# shematic_easyeda_file.net
KiCad netlist of a schematic drawn in EasyEDA
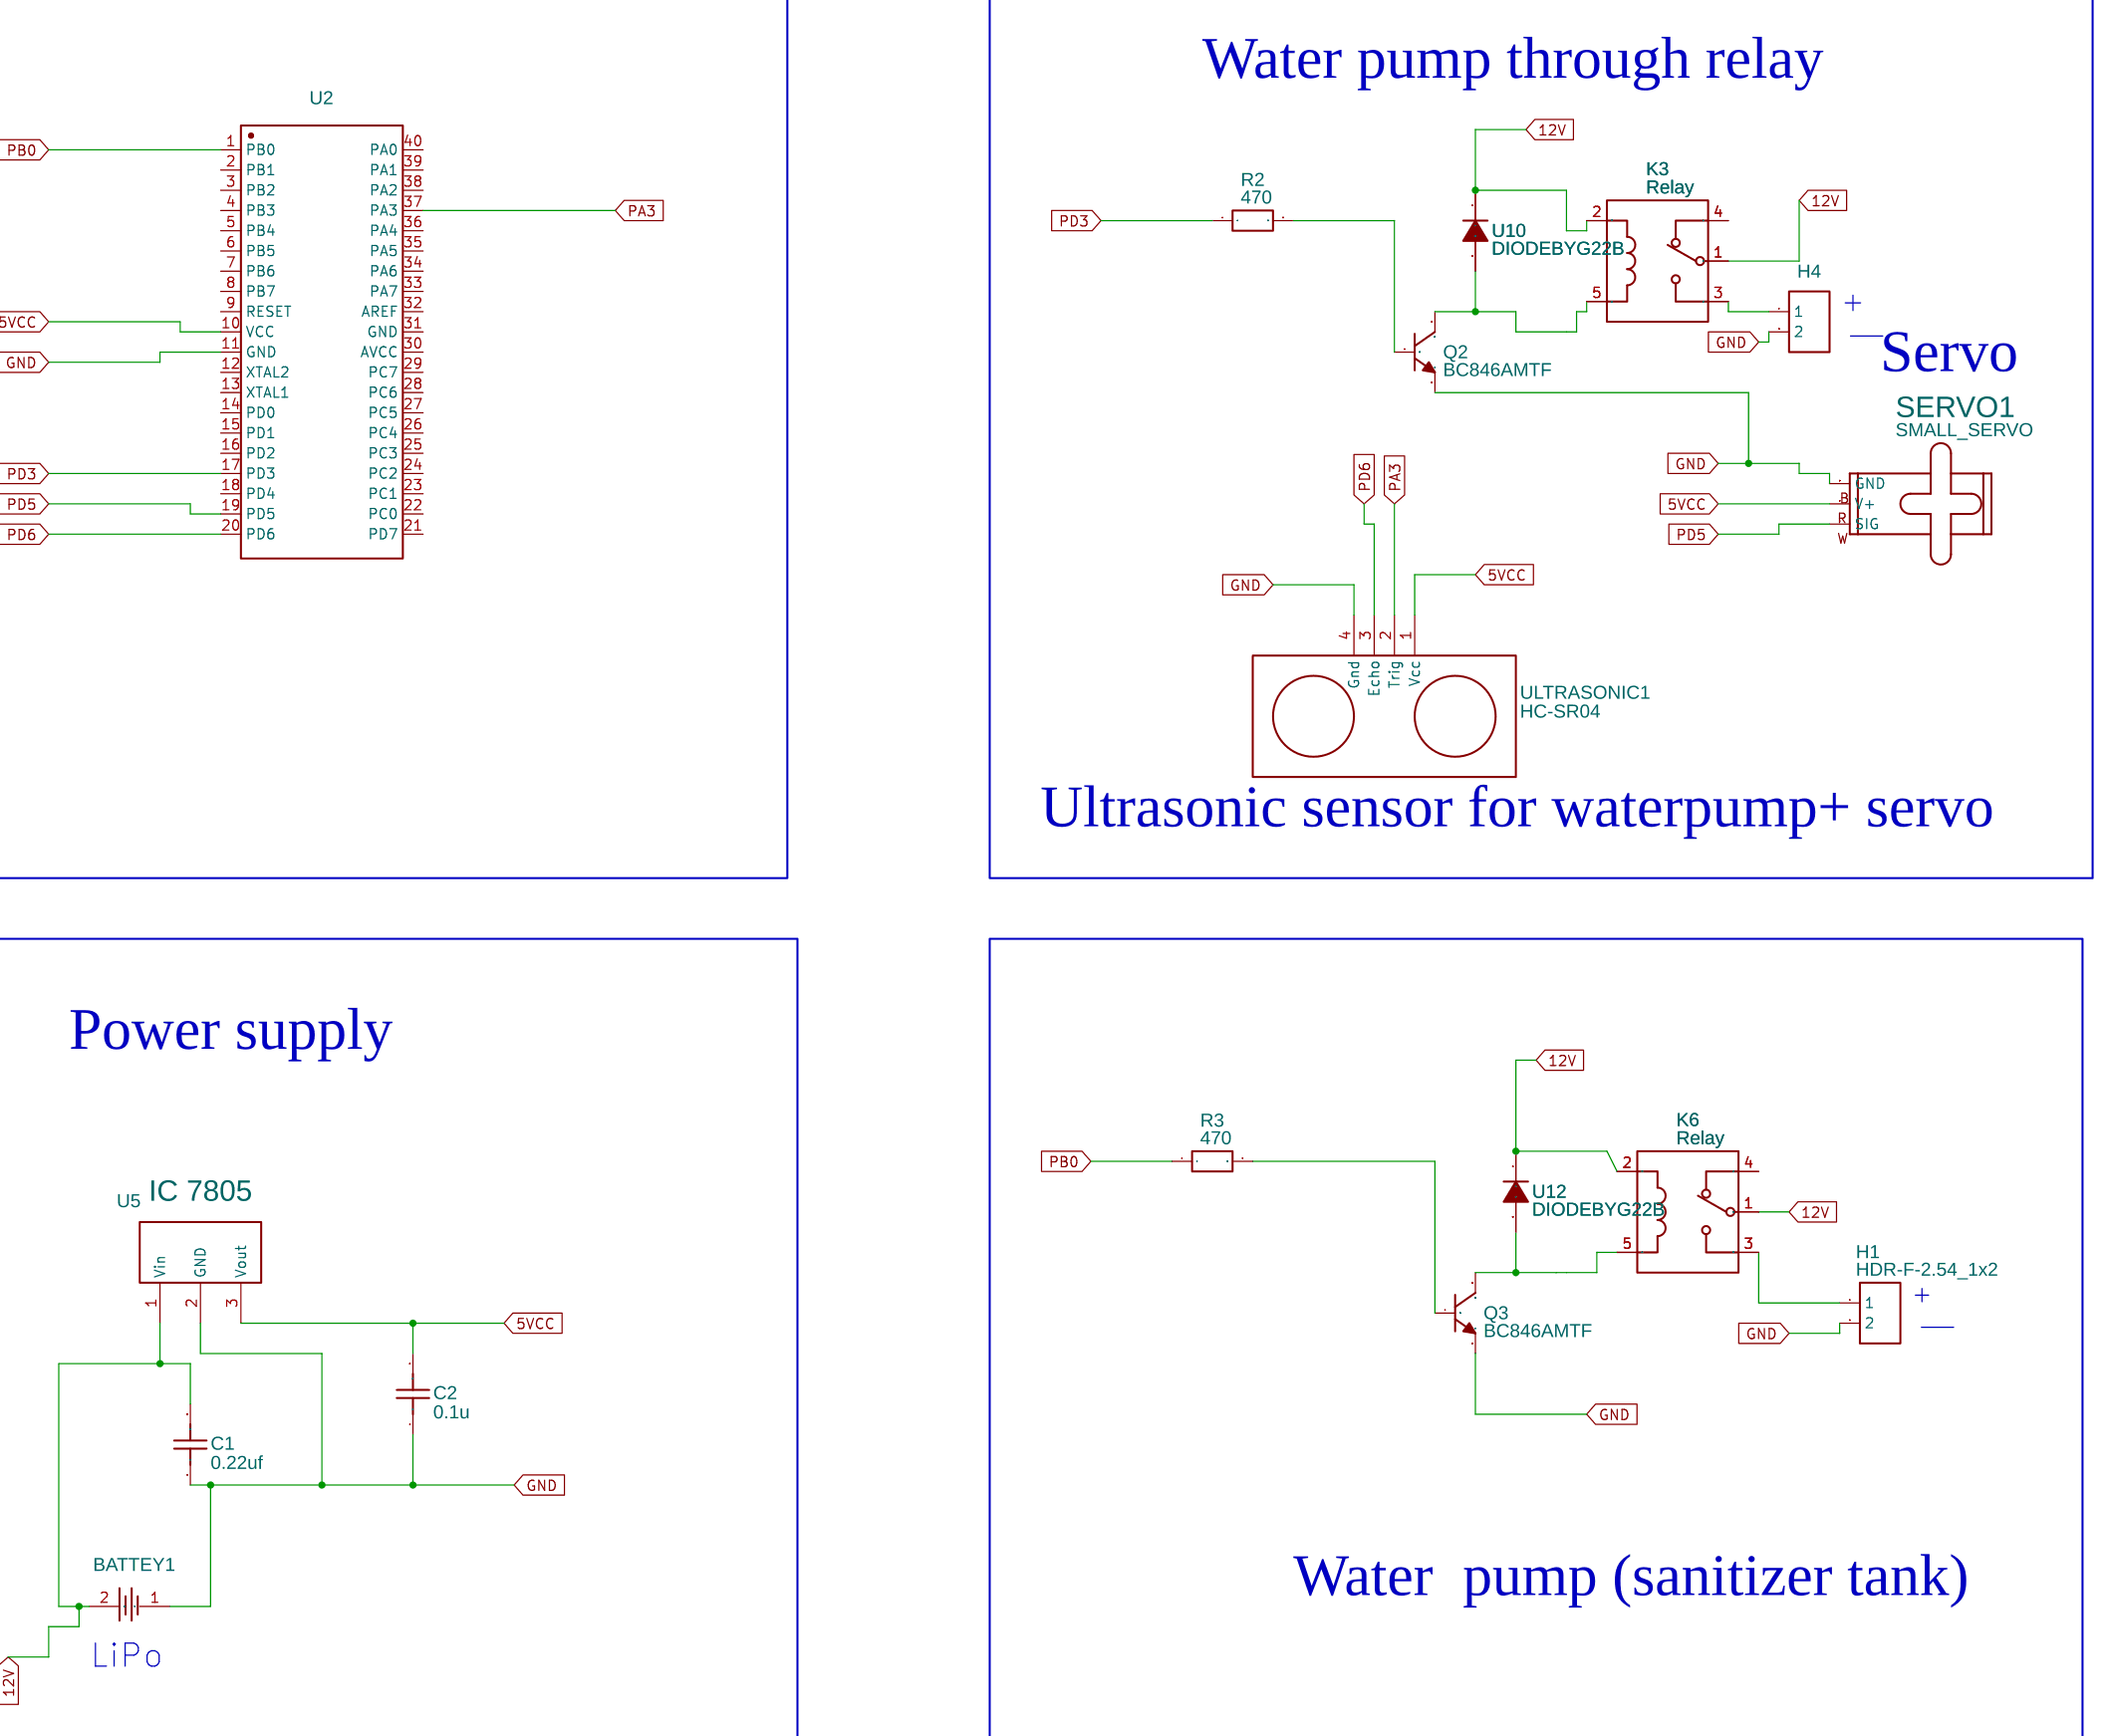
[diagram p0: schematic sheet]

(export (version "E")
  (design (tool "Eeschema 10.0.6"))
  (components
    (comp (ref "BATTEY1")
      (value "BH-18650-B1BA002")
      (fields (field (name "BOM_Supplier Part") "C2988620"))
      (libsource (lib "") (part "BH-18650-B1BA002"))
    )
    (comp (ref "C1") (value "0.22uf") (libsource (lib "") (part "C_0603_US")))
    (comp (ref "C2") (value "0.1u") (libsource (lib "") (part "C_0603_US")))
    (comp (ref "H1")
      (value "HDR-F-2.54_1x2")
      (fields (field (name "BOM_Supplier Part") "C49661"))
      (libsource (lib "") (part "HDR-F-2.54_1x2"))
    )
    (comp (ref "H4")
      (value "HDR-F-2.54_1x2")
      (fields (field (name "BOM_Supplier Part") "C49661"))
      (libsource (lib "") (part "HDR-F-2.54_1x2"))
    )
    (comp (ref "K3")
      (value "Relay")
      (fields
        (field (name "BOM_Manufacturer Part") "RelayHT3F-12VDC-SHG")
        (field (name "BOM_Supplier Part") "C22022")
      )
      (libsource (lib "") (part "Unknown_890_-685"))
    )
    (comp (ref "K6")
      (value "Relay")
      (fields
        (field (name "BOM_Manufacturer Part") "RelayHT3F-12VDC-SHG")
        (field (name "BOM_Supplier Part") "C22022")
      )
      (libsource (lib "") (part "Unknown_905_-215"))
    )
    (comp (ref "Q2")
      (value "BC846AMTF")
      (fields (field (name "BOM_Supplier Part") "C184441"))
      (libsource (lib "") (part "BC846AMTF"))
    )
    (comp (ref "Q3")
      (value "BC846AMTF")
      (fields (field (name "BOM_Supplier Part") "C184441"))
      (libsource (lib "") (part "BC846AMTF"))
    )
    (comp (ref "R2") (value "470") (libsource (lib "") (part "R_0603_EU")))
    (comp (ref "R3") (value "470") (libsource (lib "") (part "R_0603_EU")))
    (comp (ref "SERVO1") (value "SMALL_SERVO") (libsource (lib "") (part "SMALL_SERVO")))
    (comp (ref "U2")
      (value "ATMEGA32A-PU")
      (fields (field (name "BOM_Supplier Part") "C12703"))
      (libsource (lib "") (part "Unknown_225_-645"))
    )
    (comp (ref "U5")
      (value "IC 7805")
      (fields
        (field (name "BOM_Manufacturer Part") "K78X6-500R2")
        (field (name "BOM_Supplier Part") "C64019")
      )
      (libsource (lib "") (part "K78X6-500R2"))
    )
    (comp (ref "U10")
      (value "DIODEBYG22B")
      (fields
        (field (name "BOM_Manufacturer Part") "DiodeBYG22B")
        (field (name "BOM_Supplier Part") "C9900013935")
      )
      (libsource (lib "") (part "DIODEBYG22B"))
    )
    (comp (ref "U12")
      (value "DIODEBYG22B")
      (fields
        (field (name "BOM_Manufacturer Part") "DiodeBYG22B")
        (field (name "BOM_Supplier Part") "C9900013935")
      )
      (libsource (lib "") (part "DIODEBYG22B"))
    )
    (comp (ref "ULTRASONIC1") (value "HC-SR04") (libsource (lib "") (part "HC-SR04")))
  )
  (nets
    (net (code "1") (name "5VCC") (class "Default")
      (node (ref "C2") (pin "2") (pinfunction "2_2") (pintype "unspecified"))
      (node (ref "SERVO1") (pin "2") (pinfunction "V+_2") (pintype "unspecified"))
      (node (ref "U2") (pin "10") (pinfunction "VCC_10") (pintype "unspecified"))
      (node (ref "U5") (pin "3") (pinfunction "Vout_3") (pintype "unspecified"))
      (node (ref "ULTRASONIC1") (pin "1") (pinfunction "Vcc_1") (pintype "unspecified"))
    )
    (net (code "2") (name "12V") (class "Default")
      (node (ref "BATTEY1") (pin "2") (pinfunction "2_2") (pintype "input"))
      (node (ref "C1") (pin "2") (pinfunction "2_2") (pintype "unspecified"))
      (node (ref "K3") (pin "1") (pinfunction "1_1") (pintype "unspecified"))
      (node (ref "K3") (pin "2") (pinfunction "2_2") (pintype "unspecified"))
      (node (ref "K6") (pin "1") (pinfunction "1_1") (pintype "unspecified"))
      (node (ref "K6") (pin "2") (pinfunction "2_2") (pintype "unspecified"))
      (node (ref "U10") (pin "1") (pinfunction "K_1") (pintype "unspecified"))
      (node (ref "U12") (pin "1") (pinfunction "K_1") (pintype "unspecified"))
      (node (ref "U5") (pin "1") (pinfunction "Vin_1") (pintype "unspecified"))
    )
    (net (code "3") (name "GND") (class "Default")
      (node (ref "BATTEY1") (pin "1") (pinfunction "1_1") (pintype "input"))
      (node (ref "C1") (pin "1") (pinfunction "1_1") (pintype "unspecified"))
      (node (ref "C2") (pin "1") (pinfunction "1_1") (pintype "unspecified"))
      (node (ref "H1") (pin "2") (pinfunction "2_2") (pintype "input"))
      (node (ref "H4") (pin "2") (pinfunction "2_2") (pintype "input"))
      (node (ref "Q2") (pin "2") (pinfunction "E_2") (pintype "unspecified"))
      (node (ref "Q3") (pin "2") (pinfunction "E_2") (pintype "unspecified"))
      (node (ref "SERVO1") (pin "3") (pinfunction "GND_3") (pintype "unspecified"))
      (node (ref "U2") (pin "11") (pinfunction "GND_11") (pintype "unspecified"))
      (node (ref "U5") (pin "2") (pinfunction "GND_2") (pintype "unspecified"))
      (node (ref "ULTRASONIC1") (pin "4") (pinfunction "Gnd_4") (pintype "unspecified"))
    )
    (net (code "4") (name "Net-(H1-Pad1)") (class "Default")
      (node (ref "H1") (pin "1") (pinfunction "1_1") (pintype "input"))
      (node (ref "K6") (pin "3") (pinfunction "3_3") (pintype "unspecified"))
    )
    (net (code "5") (name "Net-(H4-Pad1)") (class "Default")
      (node (ref "H4") (pin "1") (pinfunction "1_1") (pintype "input"))
      (node (ref "K3") (pin "3") (pinfunction "3_3") (pintype "unspecified"))
    )
    (net (code "6") (name "Net-(Q2-B)") (class "Default")
      (node (ref "Q2") (pin "1") (pinfunction "B_1") (pintype "unspecified"))
      (node (ref "R2") (pin "2") (pinfunction "2_2") (pintype "unspecified"))
    )
    (net (code "7") (name "Net-(Q2-C)") (class "Default")
      (node (ref "K3") (pin "5") (pinfunction "5_5") (pintype "unspecified"))
      (node (ref "Q2") (pin "3") (pinfunction "C_3") (pintype "unspecified"))
      (node (ref "U10") (pin "2") (pinfunction "A_2") (pintype "unspecified"))
    )
    (net (code "8") (name "Net-(Q3-B)") (class "Default")
      (node (ref "Q3") (pin "1") (pinfunction "B_1") (pintype "unspecified"))
      (node (ref "R3") (pin "2") (pinfunction "2_2") (pintype "unspecified"))
    )
    (net (code "9") (name "Net-(Q3-C)") (class "Default")
      (node (ref "K6") (pin "5") (pinfunction "5_5") (pintype "unspecified"))
      (node (ref "Q3") (pin "3") (pinfunction "C_3") (pintype "unspecified"))
      (node (ref "U12") (pin "2") (pinfunction "A_2") (pintype "unspecified"))
    )
    (net (code "10") (name "PA3") (class "Default")
      (node (ref "U2") (pin "37") (pinfunction "PA3_37") (pintype "unspecified"))
      (node (ref "ULTRASONIC1") (pin "2") (pinfunction "Trig_2") (pintype "unspecified"))
    )
    (net (code "11") (name "PB0") (class "Default")
      (node (ref "R3") (pin "1") (pinfunction "1_1") (pintype "unspecified"))
      (node (ref "U2") (pin "1") (pinfunction "PB0_1") (pintype "unspecified"))
    )
    (net (code "12") (name "PD3") (class "Default")
      (node (ref "R2") (pin "1") (pinfunction "1_1") (pintype "unspecified"))
      (node (ref "U2") (pin "17") (pinfunction "PD3_17") (pintype "unspecified"))
    )
    (net (code "13") (name "PD5") (class "Default")
      (node (ref "SERVO1") (pin "1") (pinfunction "SIG_1") (pintype "unspecified"))
      (node (ref "U2") (pin "19") (pinfunction "PD5_19") (pintype "unspecified"))
    )
    (net (code "14") (name "PD6") (class "Default")
      (node (ref "U2") (pin "20") (pinfunction "PD6_20") (pintype "unspecified"))
      (node (ref "ULTRASONIC1") (pin "3") (pinfunction "Echo_3") (pintype "unspecified"))
    )
    (net (code "15") (name "unconnected-(K3-Pad4)") (class "Default")
      (node (ref "K3") (pin "4") (pinfunction "4_4") (pintype "unspecified"))
    )
    (net (code "16") (name "unconnected-(K6-Pad4)") (class "Default")
      (node (ref "K6") (pin "4") (pinfunction "4_4") (pintype "unspecified"))
    )
    (net (code "17") (name "unconnected-(U2-AREF-Pad32)") (class "Default")
      (node (ref "U2") (pin "32") (pinfunction "AREF_32") (pintype "unspecified"))
    )
    (net (code "18") (name "unconnected-(U2-AVCC-Pad30)") (class "Default")
      (node (ref "U2") (pin "30") (pinfunction "AVCC_30") (pintype "unspecified"))
    )
    (net (code "19") (name "unconnected-(U2-GND-Pad31)") (class "Default")
      (node (ref "U2") (pin "31") (pinfunction "GND_31") (pintype "unspecified"))
    )
    (net (code "20") (name "unconnected-(U2-PA0-Pad40)") (class "Default")
      (node (ref "U2") (pin "40") (pinfunction "PA0_40") (pintype "unspecified"))
    )
    (net (code "21") (name "unconnected-(U2-PA1-Pad39)") (class "Default")
      (node (ref "U2") (pin "39") (pinfunction "PA1_39") (pintype "unspecified"))
    )
    (net (code "22") (name "unconnected-(U2-PA2-Pad38)") (class "Default")
      (node (ref "U2") (pin "38") (pinfunction "PA2_38") (pintype "unspecified"))
    )
    (net (code "23") (name "unconnected-(U2-PA4-Pad36)") (class "Default")
      (node (ref "U2") (pin "36") (pinfunction "PA4_36") (pintype "unspecified"))
    )
    (net (code "24") (name "unconnected-(U2-PA5-Pad35)") (class "Default")
      (node (ref "U2") (pin "35") (pinfunction "PA5_35") (pintype "unspecified"))
    )
    (net (code "25") (name "unconnected-(U2-PA6-Pad34)") (class "Default")
      (node (ref "U2") (pin "34") (pinfunction "PA6_34") (pintype "unspecified"))
    )
    (net (code "26") (name "unconnected-(U2-PA7-Pad33)") (class "Default")
      (node (ref "U2") (pin "33") (pinfunction "PA7_33") (pintype "unspecified"))
    )
    (net (code "27") (name "unconnected-(U2-PB1-Pad2)") (class "Default")
      (node (ref "U2") (pin "2") (pinfunction "PB1_2") (pintype "unspecified"))
    )
    (net (code "28") (name "unconnected-(U2-PB2-Pad3)") (class "Default")
      (node (ref "U2") (pin "3") (pinfunction "PB2_3") (pintype "unspecified"))
    )
    (net (code "29") (name "unconnected-(U2-PB3-Pad4)") (class "Default")
      (node (ref "U2") (pin "4") (pinfunction "PB3_4") (pintype "unspecified"))
    )
    (net (code "30") (name "unconnected-(U2-PB4-Pad5)") (class "Default")
      (node (ref "U2") (pin "5") (pinfunction "PB4_5") (pintype "unspecified"))
    )
    (net (code "31") (name "unconnected-(U2-PB5-Pad6)") (class "Default")
      (node (ref "U2") (pin "6") (pinfunction "PB5_6") (pintype "unspecified"))
    )
    (net (code "32") (name "unconnected-(U2-PB6-Pad7)") (class "Default")
      (node (ref "U2") (pin "7") (pinfunction "PB6_7") (pintype "unspecified"))
    )
    (net (code "33") (name "unconnected-(U2-PB7-Pad8)") (class "Default")
      (node (ref "U2") (pin "8") (pinfunction "PB7_8") (pintype "unspecified"))
    )
    (net (code "34") (name "unconnected-(U2-PC0-Pad22)") (class "Default")
      (node (ref "U2") (pin "22") (pinfunction "PC0_22") (pintype "unspecified"))
    )
    (net (code "35") (name "unconnected-(U2-PC1-Pad23)") (class "Default")
      (node (ref "U2") (pin "23") (pinfunction "PC1_23") (pintype "unspecified"))
    )
    (net (code "36") (name "unconnected-(U2-PC2-Pad24)") (class "Default")
      (node (ref "U2") (pin "24") (pinfunction "PC2_24") (pintype "unspecified"))
    )
    (net (code "37") (name "unconnected-(U2-PC3-Pad25)") (class "Default")
      (node (ref "U2") (pin "25") (pinfunction "PC3_25") (pintype "unspecified"))
    )
    (net (code "38") (name "unconnected-(U2-PC4-Pad26)") (class "Default")
      (node (ref "U2") (pin "26") (pinfunction "PC4_26") (pintype "unspecified"))
    )
    (net (code "39") (name "unconnected-(U2-PC5-Pad27)") (class "Default")
      (node (ref "U2") (pin "27") (pinfunction "PC5_27") (pintype "unspecified"))
    )
    (net (code "40") (name "unconnected-(U2-PC6-Pad28)") (class "Default")
      (node (ref "U2") (pin "28") (pinfunction "PC6_28") (pintype "unspecified"))
    )
    (net (code "41") (name "unconnected-(U2-PC7-Pad29)") (class "Default")
      (node (ref "U2") (pin "29") (pinfunction "PC7_29") (pintype "unspecified"))
    )
    (net (code "42") (name "unconnected-(U2-PD0-Pad14)") (class "Default")
      (node (ref "U2") (pin "14") (pinfunction "PD0_14") (pintype "unspecified"))
    )
    (net (code "43") (name "unconnected-(U2-PD1-Pad15)") (class "Default")
      (node (ref "U2") (pin "15") (pinfunction "PD1_15") (pintype "unspecified"))
    )
    (net (code "44") (name "unconnected-(U2-PD2-Pad16)") (class "Default")
      (node (ref "U2") (pin "16") (pinfunction "PD2_16") (pintype "unspecified"))
    )
    (net (code "45") (name "unconnected-(U2-PD4-Pad18)") (class "Default")
      (node (ref "U2") (pin "18") (pinfunction "PD4_18") (pintype "unspecified"))
    )
    (net (code "46") (name "unconnected-(U2-PD7-Pad21)") (class "Default")
      (node (ref "U2") (pin "21") (pinfunction "PD7_21") (pintype "unspecified"))
    )
    (net (code "47") (name "unconnected-(U2-RESET-Pad9)") (class "Default")
      (node (ref "U2") (pin "9") (pinfunction "RESET_9") (pintype "unspecified"))
    )
    (net (code "48") (name "unconnected-(U2-XTAL1-Pad13)") (class "Default")
      (node (ref "U2") (pin "13") (pinfunction "XTAL1_13") (pintype "unspecified"))
    )
    (net (code "49") (name "unconnected-(U2-XTAL2-Pad12)") (class "Default")
      (node (ref "U2") (pin "12") (pinfunction "XTAL2_12") (pintype "unspecified"))
    )
  )
)
